# gc-1000-gps.net
KiCad netlist of a schematic drawn in EAGLE
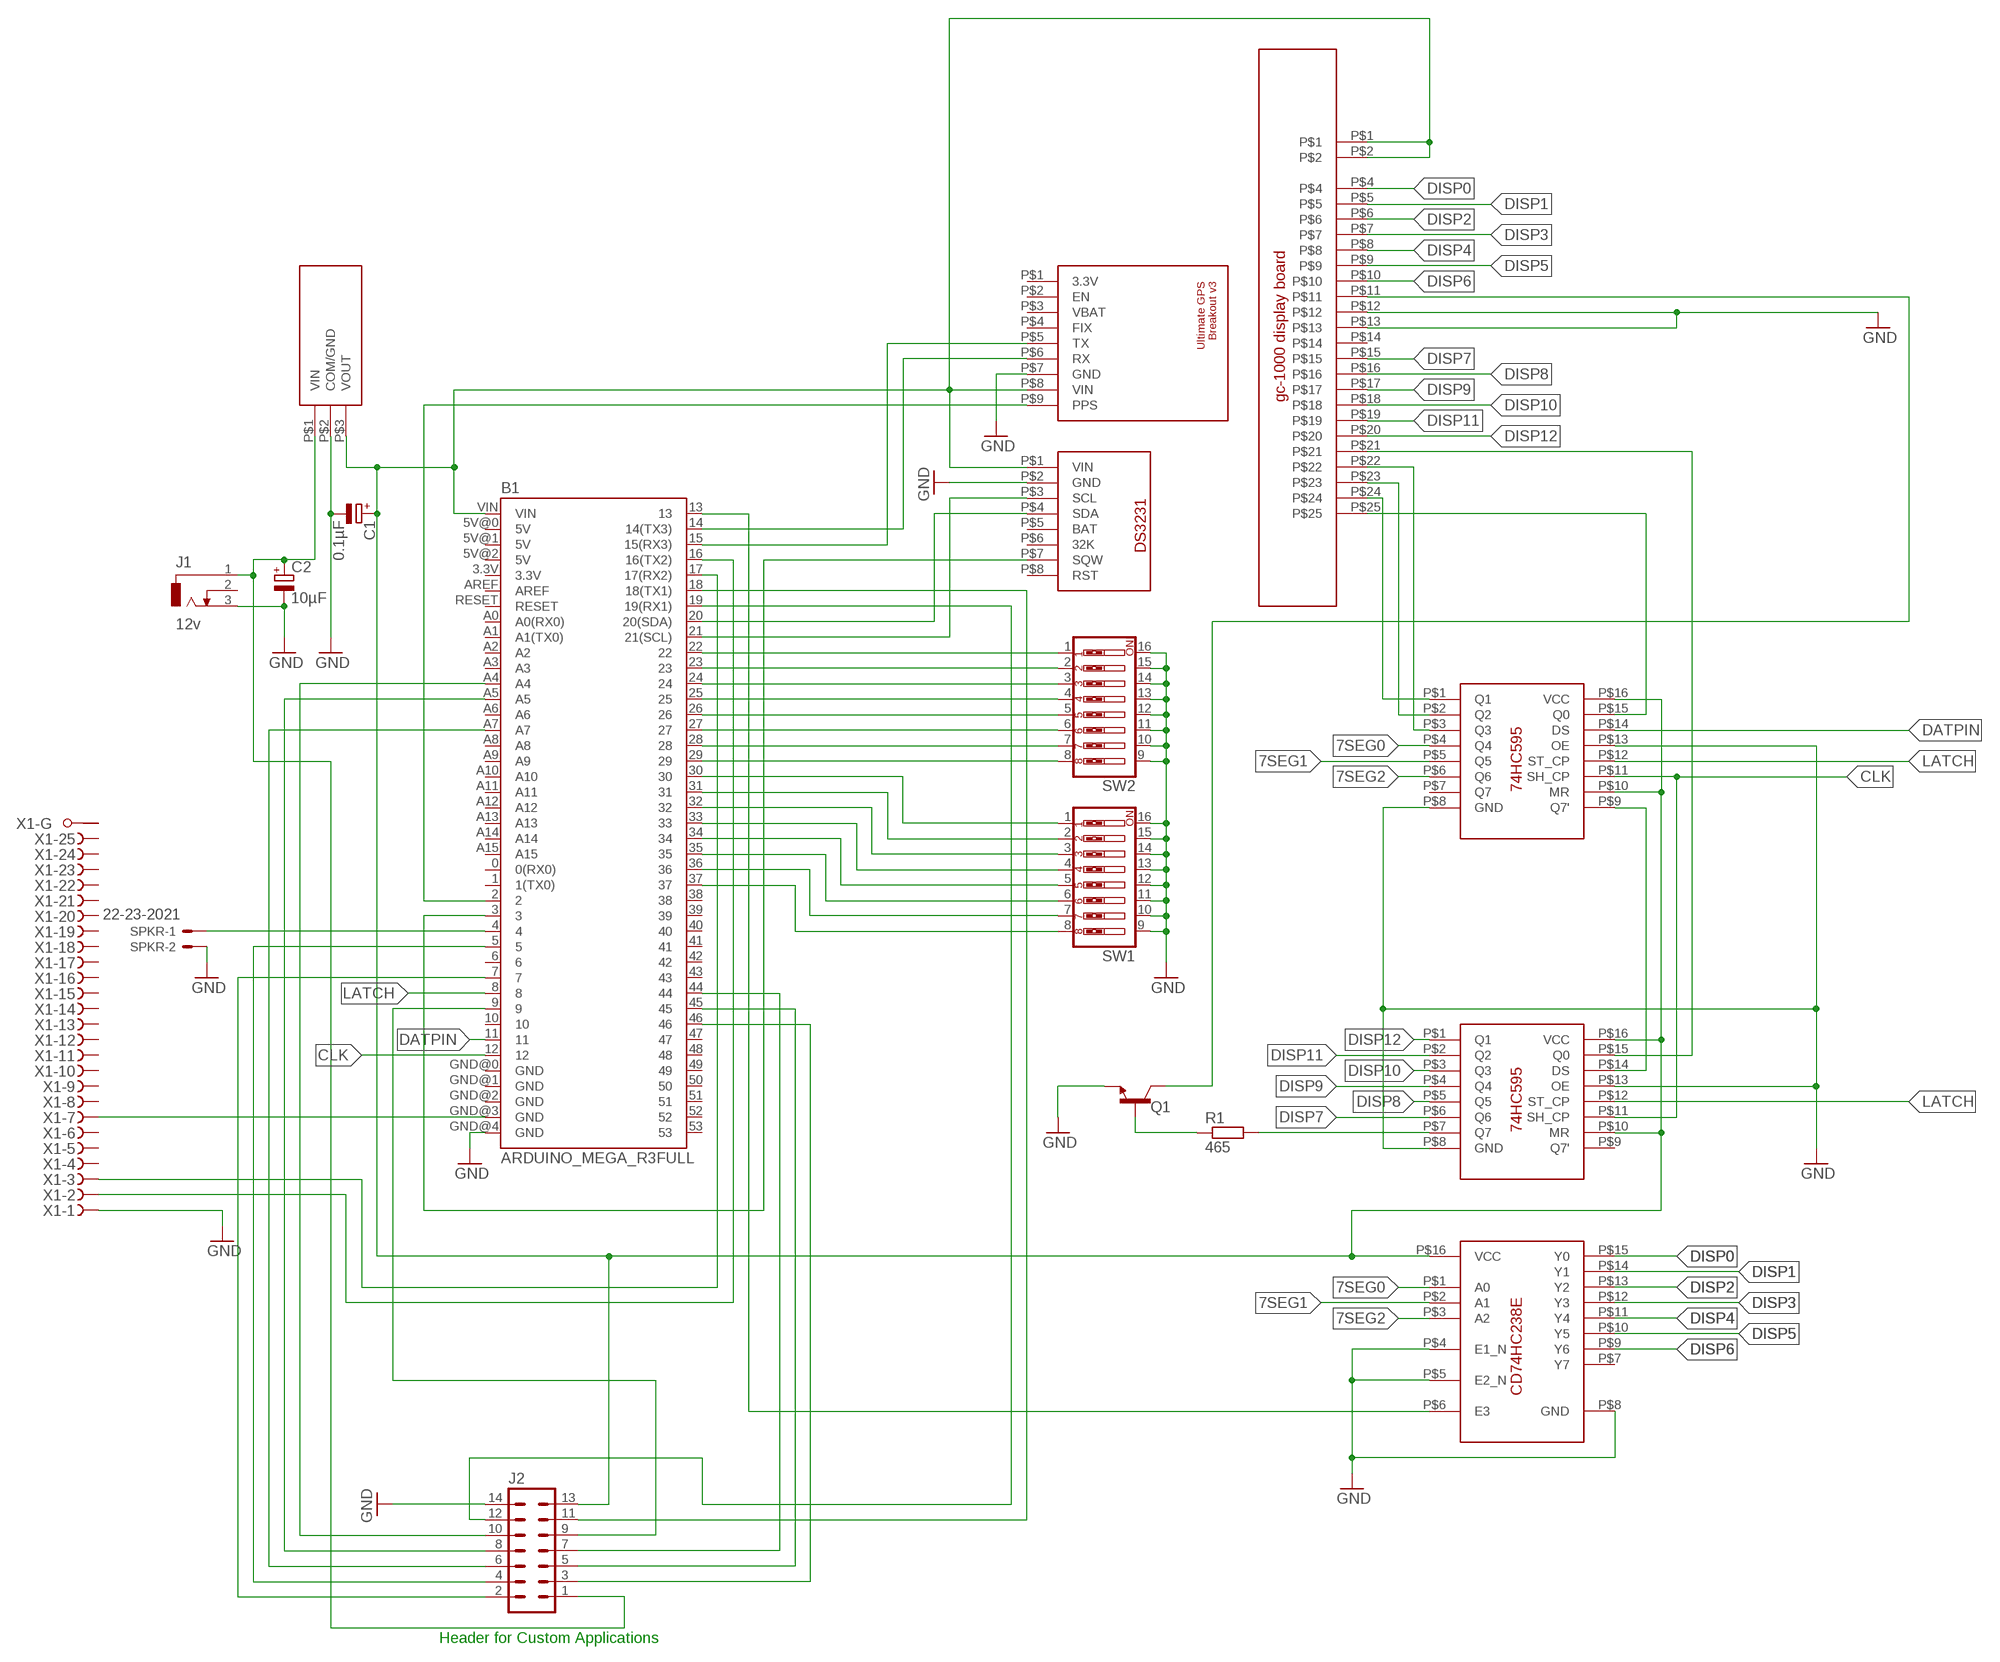
[diagram p0: schematic, sheet 1]

(export (version "E")
  (design (tool "Eeschema 10.0.6"))
  (components
    (comp (ref "B1")
      (value "ARDUINO_MEGA_R3FULL")
      (footprint "eagle-import:ARDUINO_MEGA")
      (libsource (lib "eagle-import") (part "ARDUINO_MEGA_R3FULL"))
    )
    (comp (ref "C1")
      (value "0.1µF")
      (footprint "eagle-import:E1,8-4")
      (libsource (lib "eagle-import") (part "CPOL-EUE1.8-4"))
    )
    (comp (ref "C2")
      (value "10µF")
      (footprint "eagle-import:E1,8-4")
      (libsource (lib "eagle-import") (part "CPOL-EUE1.8-4"))
    )
    (comp (ref "J1")
      (value "12v")
      (footprint "eagle-import:DCJ0303")
      (libsource (lib "eagle-import") (part "DCJ0303"))
    )
    (comp (ref "J2")
      (value "MA07-2")
      (footprint "eagle-import:MA07-2")
      (libsource (lib "eagle-import") (part "MA07-2"))
    )
    (comp (ref "Q1")
      (value "2N3904")
      (footprint "eagle-import:TO92")
      (libsource (lib "eagle-import") (part "2N3904"))
    )
    (comp (ref "R1")
      (value "465")
      (footprint "eagle-import:0207_10")
      (libsource (lib "eagle-import") (part "R-EU_0207/10"))
    )
    (comp (ref "SPKR")
      (value "22-23-2021")
      (footprint "eagle-import:22-23-2021")
      (fields (field (name "MF") "MOLEX"))
      (libsource (lib "eagle-import") (part "22-23-2021"))
    )
    (comp (ref "SW1")
      (value "SW_DIP-8")
      (footprint "eagle-import:EDG-08")
      (libsource (lib "eagle-import") (part "SW_DIP-8"))
    )
    (comp (ref "SW2")
      (value "SW_DIP-8")
      (footprint "eagle-import:EDG-08")
      (libsource (lib "eagle-import") (part "SW_DIP-8"))
    )
    (comp (ref "U$1")
      (value "PA6H-PROTO")
      (footprint "eagle-import:PA6H")
      (libsource (lib "eagle-import") (part "PA6H-PROTO"))
    )
    (comp (ref "U$2")
      (value "CD74HC238E")
      (footprint "eagle-import:CD74HC238E")
      (libsource (lib "eagle-import") (part "CD74HC238E"))
    )
    (comp (ref "U$4")
      (value "DS3231")
      (footprint "eagle-import:DS3231")
      (libsource (lib "eagle-import") (part "DS3231"))
    )
    (comp (ref "U$5")
      (value "GC-1000-DISP")
      (footprint "eagle-import:GC-1000-DISP")
      (libsource (lib "eagle-import") (part "GC-1000-DISP"))
    )
    (comp (ref "U$6")
      (value "74HC595")
      (footprint "eagle-import:74HC595")
      (libsource (lib "eagle-import") (part "74HC595"))
    )
    (comp (ref "U$7")
      (value "74HC595")
      (footprint "eagle-import:74HC595")
      (libsource (lib "eagle-import") (part "74HC595"))
    )
    (comp (ref "U1")
      (value "OKI-78SR")
      (footprint "eagle-import:OKI-78SR")
      (libsource (lib "eagle-import") (part "OKI-78SR"))
    )
    (comp (ref "X1")
      (value "F25HPS")
      (footprint "eagle-import:F25HP")
      (libsource (lib "eagle-import") (part "F25HPS"))
    )
  )
  (nets
    (net (code "1") (name "7SEG0") (class "Default")
      (node (ref "U$2") (pin "P$1") (pinfunction "A0_P$1") (pintype "bidirectional"))
      (node (ref "U$6") (pin "P$4") (pinfunction "Q4_P$4") (pintype "bidirectional"))
    )
    (net (code "2") (name "7SEG1") (class "Default")
      (node (ref "U$2") (pin "P$2") (pinfunction "A1_P$2") (pintype "bidirectional"))
      (node (ref "U$6") (pin "P$5") (pinfunction "Q5_P$5") (pintype "bidirectional"))
    )
    (net (code "3") (name "7SEG2") (class "Default")
      (node (ref "U$2") (pin "P$3") (pinfunction "A2_P$3") (pintype "bidirectional"))
      (node (ref "U$6") (pin "P$6") (pinfunction "Q6_P$6") (pintype "bidirectional"))
    )
    (net (code "4") (name "CLK") (class "Default")
      (node (ref "B1") (pin "12") (pinfunction "12_12") (pintype "bidirectional"))
      (node (ref "U$6") (pin "P$11") (pinfunction "SH_CP_P$11") (pintype "bidirectional"))
      (node (ref "U$7") (pin "P$11") (pinfunction "SH_CP_P$11") (pintype "bidirectional"))
    )
    (net (code "5") (name "DATPIN") (class "Default")
      (node (ref "B1") (pin "11") (pinfunction "11_11") (pintype "bidirectional"))
      (node (ref "U$6") (pin "P$14") (pinfunction "DS_P$14") (pintype "bidirectional"))
    )
    (net (code "6") (name "DISP0") (class "Default")
      (node (ref "U$2") (pin "P$15") (pinfunction "Y0_P$15") (pintype "bidirectional"))
      (node (ref "U$5") (pin "P$4") (pinfunction "P$4_P$4") (pintype "bidirectional"))
    )
    (net (code "7") (name "DISP1") (class "Default")
      (node (ref "U$2") (pin "P$14") (pinfunction "Y1_P$14") (pintype "bidirectional"))
      (node (ref "U$5") (pin "P$5") (pinfunction "P$5_P$5") (pintype "bidirectional"))
    )
    (net (code "8") (name "DISP2") (class "Default")
      (node (ref "U$2") (pin "P$13") (pinfunction "Y2_P$13") (pintype "bidirectional"))
      (node (ref "U$5") (pin "P$6") (pinfunction "P$6_P$6") (pintype "bidirectional"))
    )
    (net (code "9") (name "DISP3") (class "Default")
      (node (ref "U$2") (pin "P$12") (pinfunction "Y3_P$12") (pintype "bidirectional"))
      (node (ref "U$5") (pin "P$7") (pinfunction "P$7_P$7") (pintype "bidirectional"))
    )
    (net (code "10") (name "DISP4") (class "Default")
      (node (ref "U$2") (pin "P$11") (pinfunction "Y4_P$11") (pintype "bidirectional"))
      (node (ref "U$5") (pin "P$8") (pinfunction "P$8_P$8") (pintype "bidirectional"))
    )
    (net (code "11") (name "DISP5") (class "Default")
      (node (ref "U$2") (pin "P$10") (pinfunction "Y5_P$10") (pintype "bidirectional"))
      (node (ref "U$5") (pin "P$9") (pinfunction "P$9_P$9") (pintype "bidirectional"))
    )
    (net (code "12") (name "DISP6") (class "Default")
      (node (ref "U$2") (pin "P$9") (pinfunction "Y6_P$9") (pintype "bidirectional"))
      (node (ref "U$5") (pin "P$10") (pinfunction "P$10_P$10") (pintype "bidirectional"))
    )
    (net (code "13") (name "DISP7") (class "Default")
      (node (ref "U$5") (pin "P$15") (pinfunction "P$15_P$15") (pintype "bidirectional"))
      (node (ref "U$7") (pin "P$6") (pinfunction "Q6_P$6") (pintype "bidirectional"))
    )
    (net (code "14") (name "DISP8") (class "Default")
      (node (ref "U$5") (pin "P$16") (pinfunction "P$16_P$16") (pintype "bidirectional"))
      (node (ref "U$7") (pin "P$5") (pinfunction "Q5_P$5") (pintype "bidirectional"))
    )
    (net (code "15") (name "DISP9") (class "Default")
      (node (ref "U$5") (pin "P$17") (pinfunction "P$17_P$17") (pintype "bidirectional"))
      (node (ref "U$7") (pin "P$4") (pinfunction "Q4_P$4") (pintype "bidirectional"))
    )
    (net (code "16") (name "DISP10") (class "Default")
      (node (ref "U$5") (pin "P$18") (pinfunction "P$18_P$18") (pintype "bidirectional"))
      (node (ref "U$7") (pin "P$3") (pinfunction "Q3_P$3") (pintype "bidirectional"))
    )
    (net (code "17") (name "DISP11") (class "Default")
      (node (ref "U$5") (pin "P$19") (pinfunction "P$19_P$19") (pintype "bidirectional"))
      (node (ref "U$7") (pin "P$2") (pinfunction "Q2_P$2") (pintype "bidirectional"))
    )
    (net (code "18") (name "DISP12") (class "Default")
      (node (ref "U$5") (pin "P$20") (pinfunction "P$20_P$20") (pintype "bidirectional"))
      (node (ref "U$7") (pin "P$1") (pinfunction "Q1_P$1") (pintype "bidirectional"))
    )
    (net (code "19") (name "GND") (class "Default")
      (node (ref "B1") (pin "GND@4") (pinfunction "GND_GND@4") (pintype "bidirectional"))
      (node (ref "C1") (pin "-") (pinfunction "-_-") (pintype "passive"))
      (node (ref "C2") (pin "-") (pinfunction "-_-") (pintype "passive"))
      (node (ref "J1") (pin "3") (pinfunction "3_3") (pintype "passive"))
      (node (ref "J2") (pin "14") (pinfunction "14_14") (pintype "passive"))
      (node (ref "Q1") (pin "3") (pinfunction "E_3") (pintype "passive"))
      (node (ref "SPKR") (pin "2") (pinfunction "S_2") (pintype "passive"))
      (node (ref "SW1") (pin "10") (pinfunction "10_10") (pintype "passive"))
      (node (ref "SW1") (pin "11") (pinfunction "11_11") (pintype "passive"))
      (node (ref "SW1") (pin "12") (pinfunction "12_12") (pintype "passive"))
      (node (ref "SW1") (pin "13") (pinfunction "13_13") (pintype "passive"))
      (node (ref "SW1") (pin "14") (pinfunction "14_14") (pintype "passive"))
      (node (ref "SW1") (pin "15") (pinfunction "15_15") (pintype "passive"))
      (node (ref "SW1") (pin "16") (pinfunction "16_16") (pintype "passive"))
      (node (ref "SW1") (pin "9") (pinfunction "9_9") (pintype "passive"))
      (node (ref "SW2") (pin "10") (pinfunction "10_10") (pintype "passive"))
      (node (ref "SW2") (pin "11") (pinfunction "11_11") (pintype "passive"))
      (node (ref "SW2") (pin "12") (pinfunction "12_12") (pintype "passive"))
      (node (ref "SW2") (pin "13") (pinfunction "13_13") (pintype "passive"))
      (node (ref "SW2") (pin "14") (pinfunction "14_14") (pintype "passive"))
      (node (ref "SW2") (pin "15") (pinfunction "15_15") (pintype "passive"))
      (node (ref "SW2") (pin "16") (pinfunction "16_16") (pintype "passive"))
      (node (ref "SW2") (pin "9") (pinfunction "9_9") (pintype "passive"))
      (node (ref "U$1") (pin "P$7") (pinfunction "GND_P$7") (pintype "bidirectional"))
      (node (ref "U$2") (pin "P$4") (pinfunction "E1_N_P$4") (pintype "bidirectional"))
      (node (ref "U$2") (pin "P$5") (pinfunction "E2_N_P$5") (pintype "bidirectional"))
      (node (ref "U$2") (pin "P$8") (pinfunction "GND_P$8") (pintype "bidirectional"))
      (node (ref "U$4") (pin "P$2") (pinfunction "GND_P$2") (pintype "bidirectional"))
      (node (ref "U$5") (pin "P$12") (pinfunction "P$12_P$12") (pintype "bidirectional"))
      (node (ref "U$5") (pin "P$13") (pinfunction "P$13_P$13") (pintype "bidirectional"))
      (node (ref "U$6") (pin "P$13") (pinfunction "OE_P$13") (pintype "bidirectional"))
      (node (ref "U$6") (pin "P$8") (pinfunction "GND_P$8") (pintype "bidirectional"))
      (node (ref "U$7") (pin "P$13") (pinfunction "OE_P$13") (pintype "bidirectional"))
      (node (ref "U$7") (pin "P$8") (pinfunction "GND_P$8") (pintype "bidirectional"))
      (node (ref "U1") (pin "P$2") (pinfunction "COM/GND_P$2") (pintype "bidirectional"))
      (node (ref "X1") (pin "1") (pinfunction "F_1") (pintype "passive"))
    )
    (net (code "20") (name "LATCH") (class "Default")
      (node (ref "B1") (pin "8") (pinfunction "8_8") (pintype "bidirectional"))
      (node (ref "U$6") (pin "P$12") (pinfunction "ST_CP_P$12") (pintype "bidirectional"))
      (node (ref "U$7") (pin "P$12") (pinfunction "ST_CP_P$12") (pintype "bidirectional"))
    )
    (net (code "21") (name "Net-(B1-14(TX3))") (class "Default")
      (node (ref "B1") (pin "14") (pinfunction "14(TX3)_14") (pintype "bidirectional"))
      (node (ref "U$1") (pin "P$6") (pinfunction "RX_P$6") (pintype "bidirectional"))
    )
    (net (code "22") (name "Net-(B1-15(RX3))") (class "Default")
      (node (ref "B1") (pin "15") (pinfunction "15(RX3)_15") (pintype "bidirectional"))
      (node (ref "U$1") (pin "P$5") (pinfunction "TX_P$5") (pintype "bidirectional"))
    )
    (net (code "23") (name "Net-(B1-16(TX2))") (class "Default")
      (node (ref "B1") (pin "16") (pinfunction "16(TX2)_16") (pintype "bidirectional"))
      (node (ref "X1") (pin "2") (pinfunction "F_2") (pintype "passive"))
    )
    (net (code "24") (name "Net-(B1-17(RX2))") (class "Default")
      (node (ref "B1") (pin "17") (pinfunction "17(RX2)_17") (pintype "bidirectional"))
      (node (ref "X1") (pin "3") (pinfunction "F_3") (pintype "passive"))
    )
    (net (code "25") (name "Net-(B1-18(TX1))") (class "Default")
      (node (ref "B1") (pin "18") (pinfunction "18(TX1)_18") (pintype "bidirectional"))
      (node (ref "J2") (pin "11") (pinfunction "11_11") (pintype "passive"))
    )
    (net (code "26") (name "Net-(B1-19(RX1))") (class "Default")
      (node (ref "B1") (pin "19") (pinfunction "19(RX1)_19") (pintype "bidirectional"))
      (node (ref "J2") (pin "12") (pinfunction "12_12") (pintype "passive"))
    )
    (net (code "27") (name "Net-(B1-20(SDA))") (class "Default")
      (node (ref "B1") (pin "20") (pinfunction "20(SDA)_20") (pintype "bidirectional"))
      (node (ref "U$4") (pin "P$4") (pinfunction "SDA_P$4") (pintype "bidirectional"))
    )
    (net (code "28") (name "Net-(B1-21(SCL))") (class "Default")
      (node (ref "B1") (pin "21") (pinfunction "21(SCL)_21") (pintype "bidirectional"))
      (node (ref "U$4") (pin "P$3") (pinfunction "SCL_P$3") (pintype "bidirectional"))
    )
    (net (code "29") (name "Net-(B1-Pad5)") (class "Default")
      (node (ref "B1") (pin "5") (pinfunction "5_5") (pintype "bidirectional"))
      (node (ref "J2") (pin "4") (pinfunction "4_4") (pintype "passive"))
    )
    (net (code "30") (name "Net-(B1-Pad7)") (class "Default")
      (node (ref "B1") (pin "7") (pinfunction "7_7") (pintype "bidirectional"))
      (node (ref "J2") (pin "2") (pinfunction "2_2") (pintype "passive"))
    )
    (net (code "31") (name "Net-(B1-Pad9)") (class "Default")
      (node (ref "B1") (pin "9") (pinfunction "9_9") (pintype "bidirectional"))
      (node (ref "J2") (pin "9") (pinfunction "9_9") (pintype "passive"))
    )
    (net (code "32") (name "Net-(B1-Pad22)") (class "Default")
      (node (ref "B1") (pin "22") (pinfunction "22_22") (pintype "bidirectional"))
      (node (ref "SW2") (pin "1") (pinfunction "1_1") (pintype "passive"))
    )
    (net (code "33") (name "Net-(B1-Pad23)") (class "Default")
      (node (ref "B1") (pin "23") (pinfunction "23_23") (pintype "bidirectional"))
      (node (ref "SW2") (pin "2") (pinfunction "2_2") (pintype "passive"))
    )
    (net (code "34") (name "Net-(B1-Pad24)") (class "Default")
      (node (ref "B1") (pin "24") (pinfunction "24_24") (pintype "bidirectional"))
      (node (ref "SW2") (pin "3") (pinfunction "3_3") (pintype "passive"))
    )
    (net (code "35") (name "Net-(B1-Pad25)") (class "Default")
      (node (ref "B1") (pin "25") (pinfunction "25_25") (pintype "bidirectional"))
      (node (ref "SW2") (pin "4") (pinfunction "4_4") (pintype "passive"))
    )
    (net (code "36") (name "Net-(B1-Pad26)") (class "Default")
      (node (ref "B1") (pin "26") (pinfunction "26_26") (pintype "bidirectional"))
      (node (ref "SW2") (pin "5") (pinfunction "5_5") (pintype "passive"))
    )
    (net (code "37") (name "Net-(B1-Pad27)") (class "Default")
      (node (ref "B1") (pin "27") (pinfunction "27_27") (pintype "bidirectional"))
      (node (ref "SW2") (pin "6") (pinfunction "6_6") (pintype "passive"))
    )
    (net (code "38") (name "Net-(B1-Pad28)") (class "Default")
      (node (ref "B1") (pin "28") (pinfunction "28_28") (pintype "bidirectional"))
      (node (ref "SW2") (pin "7") (pinfunction "7_7") (pintype "passive"))
    )
    (net (code "39") (name "Net-(B1-Pad29)") (class "Default")
      (node (ref "B1") (pin "29") (pinfunction "29_29") (pintype "bidirectional"))
      (node (ref "SW2") (pin "8") (pinfunction "8_8") (pintype "passive"))
    )
    (net (code "40") (name "Net-(B1-Pad30)") (class "Default")
      (node (ref "B1") (pin "30") (pinfunction "30_30") (pintype "bidirectional"))
      (node (ref "SW1") (pin "1") (pinfunction "1_1") (pintype "passive"))
    )
    (net (code "41") (name "Net-(B1-Pad31)") (class "Default")
      (node (ref "B1") (pin "31") (pinfunction "31_31") (pintype "bidirectional"))
      (node (ref "SW1") (pin "2") (pinfunction "2_2") (pintype "passive"))
    )
    (net (code "42") (name "Net-(B1-Pad32)") (class "Default")
      (node (ref "B1") (pin "32") (pinfunction "32_32") (pintype "bidirectional"))
      (node (ref "SW1") (pin "3") (pinfunction "3_3") (pintype "passive"))
    )
    (net (code "43") (name "Net-(B1-Pad33)") (class "Default")
      (node (ref "B1") (pin "33") (pinfunction "33_33") (pintype "bidirectional"))
      (node (ref "SW1") (pin "4") (pinfunction "4_4") (pintype "passive"))
    )
    (net (code "44") (name "Net-(B1-Pad34)") (class "Default")
      (node (ref "B1") (pin "34") (pinfunction "34_34") (pintype "bidirectional"))
      (node (ref "SW1") (pin "5") (pinfunction "5_5") (pintype "passive"))
    )
    (net (code "45") (name "Net-(B1-Pad35)") (class "Default")
      (node (ref "B1") (pin "35") (pinfunction "35_35") (pintype "bidirectional"))
      (node (ref "SW1") (pin "6") (pinfunction "6_6") (pintype "passive"))
    )
    (net (code "46") (name "Net-(B1-Pad36)") (class "Default")
      (node (ref "B1") (pin "36") (pinfunction "36_36") (pintype "bidirectional"))
      (node (ref "SW1") (pin "7") (pinfunction "7_7") (pintype "passive"))
    )
    (net (code "47") (name "Net-(B1-Pad37)") (class "Default")
      (node (ref "B1") (pin "37") (pinfunction "37_37") (pintype "bidirectional"))
      (node (ref "SW1") (pin "8") (pinfunction "8_8") (pintype "passive"))
    )
    (net (code "48") (name "Net-(B1-Pad44)") (class "Default")
      (node (ref "B1") (pin "44") (pinfunction "44_44") (pintype "bidirectional"))
      (node (ref "J2") (pin "7") (pinfunction "7_7") (pintype "passive"))
    )
    (net (code "49") (name "Net-(B1-Pad45)") (class "Default")
      (node (ref "B1") (pin "45") (pinfunction "45_45") (pintype "bidirectional"))
      (node (ref "J2") (pin "5") (pinfunction "5_5") (pintype "passive"))
    )
    (net (code "50") (name "Net-(B1-Pad46)") (class "Default")
      (node (ref "B1") (pin "46") (pinfunction "46_46") (pintype "bidirectional"))
      (node (ref "J2") (pin "3") (pinfunction "3_3") (pintype "passive"))
    )
    (net (code "51") (name "Net-(B1-PadA4)") (class "Default")
      (node (ref "B1") (pin "A4") (pinfunction "A4_A4") (pintype "bidirectional"))
      (node (ref "J2") (pin "10") (pinfunction "10_10") (pintype "passive"))
    )
    (net (code "52") (name "Net-(B1-PadA5)") (class "Default")
      (node (ref "B1") (pin "A5") (pinfunction "A5_A5") (pintype "bidirectional"))
      (node (ref "J2") (pin "8") (pinfunction "8_8") (pintype "passive"))
    )
    (net (code "53") (name "Net-(B1-PadA7)") (class "Default")
      (node (ref "B1") (pin "A7") (pinfunction "A7_A7") (pintype "bidirectional"))
      (node (ref "J2") (pin "6") (pinfunction "6_6") (pintype "passive"))
    )
    (net (code "54") (name "Net-(Q1-B)") (class "Default")
      (node (ref "Q1") (pin "2") (pinfunction "B_2") (pintype "passive"))
      (node (ref "R1") (pin "1") (pinfunction "1_1") (pintype "passive"))
    )
    (net (code "55") (name "Net-(Q1-C)") (class "Default")
      (node (ref "Q1") (pin "1") (pinfunction "C_1") (pintype "passive"))
      (node (ref "U$5") (pin "P$11") (pinfunction "P$11_P$11") (pintype "bidirectional"))
    )
    (net (code "56") (name "Net-(SPKRA-S)") (class "Default")
      (node (ref "B1") (pin "4") (pinfunction "4_4") (pintype "bidirectional"))
      (node (ref "SPKR") (pin "1") (pinfunction "S_1") (pintype "passive"))
    )
    (net (code "57") (name "Net-(U$1-PPS)") (class "Default")
      (node (ref "B1") (pin "2") (pinfunction "2_2") (pintype "bidirectional"))
      (node (ref "U$1") (pin "P$9") (pinfunction "PPS_P$9") (pintype "bidirectional"))
    )
    (net (code "58") (name "Net-(U$1-VIN)") (class "Default")
      (node (ref "B1") (pin "VIN") (pinfunction "VIN_VIN") (pintype "bidirectional"))
      (node (ref "C1") (pin "+") (pinfunction "+_+") (pintype "passive"))
      (node (ref "J2") (pin "13") (pinfunction "13_13") (pintype "passive"))
      (node (ref "U$1") (pin "P$8") (pinfunction "VIN_P$8") (pintype "bidirectional"))
      (node (ref "U$2") (pin "P$16") (pinfunction "VCC_P$16") (pintype "bidirectional"))
      (node (ref "U$4") (pin "P$1") (pinfunction "VIN_P$1") (pintype "bidirectional"))
      (node (ref "U$5") (pin "P$1") (pinfunction "P$1_P$1") (pintype "bidirectional"))
      (node (ref "U$5") (pin "P$2") (pinfunction "P$2_P$2") (pintype "bidirectional"))
      (node (ref "U$6") (pin "P$10") (pinfunction "MR_P$10") (pintype "bidirectional"))
      (node (ref "U$6") (pin "P$16") (pinfunction "VCC_P$16") (pintype "bidirectional"))
      (node (ref "U$7") (pin "P$10") (pinfunction "MR_P$10") (pintype "bidirectional"))
      (node (ref "U$7") (pin "P$16") (pinfunction "VCC_P$16") (pintype "bidirectional"))
      (node (ref "U1") (pin "P$3") (pinfunction "VOUT_P$3") (pintype "bidirectional"))
    )
    (net (code "59") (name "Net-(U$2-E3)") (class "Default")
      (node (ref "B1") (pin "13") (pinfunction "13_13") (pintype "bidirectional"))
      (node (ref "U$2") (pin "P$6") (pinfunction "E3_P$6") (pintype "bidirectional"))
    )
    (net (code "60") (name "Net-(U$4-SQW)") (class "Default")
      (node (ref "B1") (pin "3") (pinfunction "3_3") (pintype "bidirectional"))
      (node (ref "U$4") (pin "P$7") (pinfunction "SQW_P$7") (pintype "bidirectional"))
    )
    (net (code "61") (name "Net-(U$6-Q0)") (class "Default")
      (node (ref "U$5") (pin "P$25") (pinfunction "P$25_P$25") (pintype "bidirectional"))
      (node (ref "U$6") (pin "P$15") (pinfunction "Q0_P$15") (pintype "bidirectional"))
    )
    (net (code "62") (name "Net-(U$6-Q1)") (class "Default")
      (node (ref "U$5") (pin "P$24") (pinfunction "P$24_P$24") (pintype "bidirectional"))
      (node (ref "U$6") (pin "P$1") (pinfunction "Q1_P$1") (pintype "bidirectional"))
    )
    (net (code "63") (name "Net-(U$6-Q2)") (class "Default")
      (node (ref "U$5") (pin "P$23") (pinfunction "P$23_P$23") (pintype "bidirectional"))
      (node (ref "U$6") (pin "P$2") (pinfunction "Q2_P$2") (pintype "bidirectional"))
    )
    (net (code "64") (name "Net-(U$6-Q3)") (class "Default")
      (node (ref "U$5") (pin "P$22") (pinfunction "P$22_P$22") (pintype "bidirectional"))
      (node (ref "U$6") (pin "P$3") (pinfunction "Q3_P$3") (pintype "bidirectional"))
    )
    (net (code "65") (name "Net-(U$6-Q7')") (class "Default")
      (node (ref "U$6") (pin "P$9") (pinfunction "Q7'_P$9") (pintype "bidirectional"))
      (node (ref "U$7") (pin "P$14") (pinfunction "DS_P$14") (pintype "bidirectional"))
    )
    (net (code "66") (name "Net-(U$7-Q0)") (class "Default")
      (node (ref "U$5") (pin "P$21") (pinfunction "P$21_P$21") (pintype "bidirectional"))
      (node (ref "U$7") (pin "P$15") (pinfunction "Q0_P$15") (pintype "bidirectional"))
    )
    (net (code "67") (name "Net-(U$7-Q7)") (class "Default")
      (node (ref "R1") (pin "2") (pinfunction "2_2") (pintype "passive"))
      (node (ref "U$7") (pin "P$7") (pinfunction "Q7_P$7") (pintype "bidirectional"))
    )
    (net (code "68") (name "Net-(U1-VIN)") (class "Default")
      (node (ref "C2") (pin "+") (pinfunction "+_+") (pintype "passive"))
      (node (ref "J1") (pin "1") (pinfunction "1_1") (pintype "passive"))
      (node (ref "J2") (pin "1") (pinfunction "1_1") (pintype "passive"))
      (node (ref "U1") (pin "P$1") (pinfunction "VIN_P$1") (pintype "bidirectional"))
    )
    (net (code "69") (name "Net-(X1W-F)") (class "Default")
      (node (ref "B1") (pin "GND@3") (pinfunction "GND_GND@3") (pintype "bidirectional"))
      (node (ref "X1") (pin "7") (pinfunction "F_7") (pintype "passive"))
    )
    (net (code "70") (name "unconnected-(B1-0(RX0)-Pad0)") (class "Default")
      (node (ref "B1") (pin "0") (pinfunction "0(RX0)_0") (pintype "bidirectional"))
    )
    (net (code "71") (name "unconnected-(B1-1(TX0)-Pad1)") (class "Default")
      (node (ref "B1") (pin "1") (pinfunction "1(TX0)_1") (pintype "bidirectional"))
    )
    (net (code "72") (name "unconnected-(B1-5V-Pad5V@0)") (class "Default")
      (node (ref "B1") (pin "5V@0") (pinfunction "5V_5V@0") (pintype "bidirectional"))
    )
    (net (code "73") (name "unconnected-(B1-5V-Pad5V@1)") (class "Default")
      (node (ref "B1") (pin "5V@1") (pinfunction "5V_5V@1") (pintype "bidirectional"))
    )
    (net (code "74") (name "unconnected-(B1-5V-Pad5V@2)") (class "Default")
      (node (ref "B1") (pin "5V@2") (pinfunction "5V_5V@2") (pintype "bidirectional"))
    )
    (net (code "75") (name "unconnected-(B1-A0(RX0)-PadA0)") (class "Default")
      (node (ref "B1") (pin "A0") (pinfunction "A0(RX0)_A0") (pintype "bidirectional"))
    )
    (net (code "76") (name "unconnected-(B1-A1(TX0)-PadA1)") (class "Default")
      (node (ref "B1") (pin "A1") (pinfunction "A1(TX0)_A1") (pintype "bidirectional"))
    )
    (net (code "77") (name "unconnected-(B1-GND-PadGND@0)") (class "Default")
      (node (ref "B1") (pin "GND@0") (pinfunction "GND_GND@0") (pintype "bidirectional"))
    )
    (net (code "78") (name "unconnected-(B1-GND-PadGND@1)") (class "Default")
      (node (ref "B1") (pin "GND@1") (pinfunction "GND_GND@1") (pintype "bidirectional"))
    )
    (net (code "79") (name "unconnected-(B1-GND-PadGND@2)") (class "Default")
      (node (ref "B1") (pin "GND@2") (pinfunction "GND_GND@2") (pintype "bidirectional"))
    )
    (net (code "80") (name "unconnected-(B1-Pad3.3V)") (class "Default")
      (node (ref "B1") (pin "3.3V") (pinfunction "3.3V_3.3V") (pintype "bidirectional"))
    )
    (net (code "81") (name "unconnected-(B1-Pad6)") (class "Default")
      (node (ref "B1") (pin "6") (pinfunction "6_6") (pintype "bidirectional"))
    )
    (net (code "82") (name "unconnected-(B1-Pad10)") (class "Default")
      (node (ref "B1") (pin "10") (pinfunction "10_10") (pintype "bidirectional"))
    )
    (net (code "83") (name "unconnected-(B1-Pad38)") (class "Default")
      (node (ref "B1") (pin "38") (pinfunction "38_38") (pintype "bidirectional"))
    )
    (net (code "84") (name "unconnected-(B1-Pad39)") (class "Default")
      (node (ref "B1") (pin "39") (pinfunction "39_39") (pintype "bidirectional"))
    )
    (net (code "85") (name "unconnected-(B1-Pad40)") (class "Default")
      (node (ref "B1") (pin "40") (pinfunction "40_40") (pintype "bidirectional"))
    )
    (net (code "86") (name "unconnected-(B1-Pad41)") (class "Default")
      (node (ref "B1") (pin "41") (pinfunction "41_41") (pintype "bidirectional"))
    )
    (net (code "87") (name "unconnected-(B1-Pad42)") (class "Default")
      (node (ref "B1") (pin "42") (pinfunction "42_42") (pintype "bidirectional"))
    )
    (net (code "88") (name "unconnected-(B1-Pad43)") (class "Default")
      (node (ref "B1") (pin "43") (pinfunction "43_43") (pintype "bidirectional"))
    )
    (net (code "89") (name "unconnected-(B1-Pad47)") (class "Default")
      (node (ref "B1") (pin "47") (pinfunction "47_47") (pintype "bidirectional"))
    )
    (net (code "90") (name "unconnected-(B1-Pad48)") (class "Default")
      (node (ref "B1") (pin "48") (pinfunction "48_48") (pintype "bidirectional"))
    )
    (net (code "91") (name "unconnected-(B1-Pad49)") (class "Default")
      (node (ref "B1") (pin "49") (pinfunction "49_49") (pintype "bidirectional"))
    )
    (net (code "92") (name "unconnected-(B1-Pad50)") (class "Default")
      (node (ref "B1") (pin "50") (pinfunction "50_50") (pintype "bidirectional"))
    )
    (net (code "93") (name "unconnected-(B1-Pad51)") (class "Default")
      (node (ref "B1") (pin "51") (pinfunction "51_51") (pintype "bidirectional"))
    )
    (net (code "94") (name "unconnected-(B1-Pad52)") (class "Default")
      (node (ref "B1") (pin "52") (pinfunction "52_52") (pintype "bidirectional"))
    )
    (net (code "95") (name "unconnected-(B1-Pad53)") (class "Default")
      (node (ref "B1") (pin "53") (pinfunction "53_53") (pintype "bidirectional"))
    )
    (net (code "96") (name "unconnected-(B1-PadA2)") (class "Default")
      (node (ref "B1") (pin "A2") (pinfunction "A2_A2") (pintype "bidirectional"))
    )
    (net (code "97") (name "unconnected-(B1-PadA3)") (class "Default")
      (node (ref "B1") (pin "A3") (pinfunction "A3_A3") (pintype "bidirectional"))
    )
    (net (code "98") (name "unconnected-(B1-PadA6)") (class "Default")
      (node (ref "B1") (pin "A6") (pinfunction "A6_A6") (pintype "bidirectional"))
    )
    (net (code "99") (name "unconnected-(B1-PadA8)") (class "Default")
      (node (ref "B1") (pin "A8") (pinfunction "A8_A8") (pintype "bidirectional"))
    )
    (net (code "100") (name "unconnected-(B1-PadA9)") (class "Default")
      (node (ref "B1") (pin "A9") (pinfunction "A9_A9") (pintype "bidirectional"))
    )
    (net (code "101") (name "unconnected-(B1-PadA10)") (class "Default")
      (node (ref "B1") (pin "A10") (pinfunction "A10_A10") (pintype "bidirectional"))
    )
    (net (code "102") (name "unconnected-(B1-PadA11)") (class "Default")
      (node (ref "B1") (pin "A11") (pinfunction "A11_A11") (pintype "bidirectional"))
    )
    (net (code "103") (name "unconnected-(B1-PadA12)") (class "Default")
      (node (ref "B1") (pin "A12") (pinfunction "A12_A12") (pintype "bidirectional"))
    )
    (net (code "104") (name "unconnected-(B1-PadA13)") (class "Default")
      (node (ref "B1") (pin "A13") (pinfunction "A13_A13") (pintype "bidirectional"))
    )
    (net (code "105") (name "unconnected-(B1-PadA14)") (class "Default")
      (node (ref "B1") (pin "A14") (pinfunction "A14_A14") (pintype "bidirectional"))
    )
    (net (code "106") (name "unconnected-(B1-PadA15)") (class "Default")
      (node (ref "B1") (pin "A15") (pinfunction "A15_A15") (pintype "bidirectional"))
    )
    (net (code "107") (name "unconnected-(B1-PadAREF)") (class "Default")
      (node (ref "B1") (pin "AREF") (pinfunction "AREF_AREF") (pintype "bidirectional"))
    )
    (net (code "108") (name "unconnected-(B1-PadRESET)") (class "Default")
      (node (ref "B1") (pin "RESET") (pinfunction "RESET_RESET") (pintype "bidirectional"))
    )
    (net (code "109") (name "unconnected-(J1-Pad2)") (class "Default")
      (node (ref "J1") (pin "2") (pinfunction "2_2") (pintype "passive"))
    )
    (net (code "110") (name "unconnected-(U$1-3.3V-PadP$1)") (class "Default")
      (node (ref "U$1") (pin "P$1") (pinfunction "3.3V_P$1") (pintype "bidirectional"))
    )
    (net (code "111") (name "unconnected-(U$1-EN-PadP$2)") (class "Default")
      (node (ref "U$1") (pin "P$2") (pinfunction "EN_P$2") (pintype "bidirectional"))
    )
    (net (code "112") (name "unconnected-(U$1-FIX-PadP$4)") (class "Default")
      (node (ref "U$1") (pin "P$4") (pinfunction "FIX_P$4") (pintype "bidirectional"))
    )
    (net (code "113") (name "unconnected-(U$1-VBAT-PadP$3)") (class "Default")
      (node (ref "U$1") (pin "P$3") (pinfunction "VBAT_P$3") (pintype "bidirectional"))
    )
    (net (code "114") (name "unconnected-(U$2-Y7-PadP$7)") (class "Default")
      (node (ref "U$2") (pin "P$7") (pinfunction "Y7_P$7") (pintype "bidirectional"))
    )
    (net (code "115") (name "unconnected-(U$4-32K-PadP$6)") (class "Default")
      (node (ref "U$4") (pin "P$6") (pinfunction "32K_P$6") (pintype "bidirectional"))
    )
    (net (code "116") (name "unconnected-(U$4-BAT-PadP$5)") (class "Default")
      (node (ref "U$4") (pin "P$5") (pinfunction "BAT_P$5") (pintype "bidirectional"))
    )
    (net (code "117") (name "unconnected-(U$4-RST-PadP$8)") (class "Default")
      (node (ref "U$4") (pin "P$8") (pinfunction "RST_P$8") (pintype "bidirectional"))
    )
    (net (code "118") (name "unconnected-(U$5-PadP$14)") (class "Default")
      (node (ref "U$5") (pin "P$14") (pinfunction "P$14_P$14") (pintype "bidirectional"))
    )
    (net (code "119") (name "unconnected-(U$6-Q7-PadP$7)") (class "Default")
      (node (ref "U$6") (pin "P$7") (pinfunction "Q7_P$7") (pintype "bidirectional"))
    )
    (net (code "120") (name "unconnected-(U$7-Q7'-PadP$9)") (class "Default")
      (node (ref "U$7") (pin "P$9") (pinfunction "Q7'_P$9") (pintype "bidirectional"))
    )
    (net (code "121") (name "unconnected-(X1-PadG1)") (class "Default")
      (node (ref "X1") (pin "G1") (pinfunction "G1_G1") (pintype "passive"))
    )
    (net (code "122") (name "unconnected-(X1-PadG2)") (class "Default")
      (node (ref "X1") (pin "G2") (pinfunction "G2_G2") (pintype "passive"))
    )
    (net (code "123") (name "unconnected-(X1B-F-Pad10)") (class "Default")
      (node (ref "X1") (pin "10") (pinfunction "F_10") (pintype "passive"))
    )
    (net (code "124") (name "unconnected-(X1C-F-Pad11)") (class "Default")
      (node (ref "X1") (pin "11") (pinfunction "F_11") (pintype "passive"))
    )
    (net (code "125") (name "unconnected-(X1D-F-Pad12)") (class "Default")
      (node (ref "X1") (pin "12") (pinfunction "F_12") (pintype "passive"))
    )
    (net (code "126") (name "unconnected-(X1E-F-Pad13)") (class "Default")
      (node (ref "X1") (pin "13") (pinfunction "F_13") (pintype "passive"))
    )
    (net (code "127") (name "unconnected-(X1F-F-Pad14)") (class "Default")
      (node (ref "X1") (pin "14") (pinfunction "F_14") (pintype "passive"))
    )
    (net (code "128") (name "unconnected-(X1G-F-Pad15)") (class "Default")
      (node (ref "X1") (pin "15") (pinfunction "F_15") (pintype "passive"))
    )
    (net (code "129") (name "unconnected-(X1H-F-Pad16)") (class "Default")
      (node (ref "X1") (pin "16") (pinfunction "F_16") (pintype "passive"))
    )
    (net (code "130") (name "unconnected-(X1I-F-Pad17)") (class "Default")
      (node (ref "X1") (pin "17") (pinfunction "F_17") (pintype "passive"))
    )
    (net (code "131") (name "unconnected-(X1J-F-Pad18)") (class "Default")
      (node (ref "X1") (pin "18") (pinfunction "F_18") (pintype "passive"))
    )
    (net (code "132") (name "unconnected-(X1K-F-Pad19)") (class "Default")
      (node (ref "X1") (pin "19") (pinfunction "F_19") (pintype "passive"))
    )
    (net (code "133") (name "unconnected-(X1M-F-Pad20)") (class "Default")
      (node (ref "X1") (pin "20") (pinfunction "F_20") (pintype "passive"))
    )
    (net (code "134") (name "unconnected-(X1N-F-Pad21)") (class "Default")
      (node (ref "X1") (pin "21") (pinfunction "F_21") (pintype "passive"))
    )
    (net (code "135") (name "unconnected-(X1O-F-Pad22)") (class "Default")
      (node (ref "X1") (pin "22") (pinfunction "F_22") (pintype "passive"))
    )
    (net (code "136") (name "unconnected-(X1P-F-Pad23)") (class "Default")
      (node (ref "X1") (pin "23") (pinfunction "F_23") (pintype "passive"))
    )
    (net (code "137") (name "unconnected-(X1Q-F-Pad24)") (class "Default")
      (node (ref "X1") (pin "24") (pinfunction "F_24") (pintype "passive"))
    )
    (net (code "138") (name "unconnected-(X1R-F-Pad25)") (class "Default")
      (node (ref "X1") (pin "25") (pinfunction "F_25") (pintype "passive"))
    )
    (net (code "139") (name "unconnected-(X1T-F-Pad4)") (class "Default")
      (node (ref "X1") (pin "4") (pinfunction "F_4") (pintype "passive"))
    )
    (net (code "140") (name "unconnected-(X1U-F-Pad5)") (class "Default")
      (node (ref "X1") (pin "5") (pinfunction "F_5") (pintype "passive"))
    )
    (net (code "141") (name "unconnected-(X1V-F-Pad6)") (class "Default")
      (node (ref "X1") (pin "6") (pinfunction "F_6") (pintype "passive"))
    )
    (net (code "142") (name "unconnected-(X1X-F-Pad8)") (class "Default")
      (node (ref "X1") (pin "8") (pinfunction "F_8") (pintype "passive"))
    )
    (net (code "143") (name "unconnected-(X1Y-F-Pad9)") (class "Default")
      (node (ref "X1") (pin "9") (pinfunction "F_9") (pintype "passive"))
    )
  )
)
